# aux_powers.net
KiCad netlist of a schematic drawn in Altium Designer
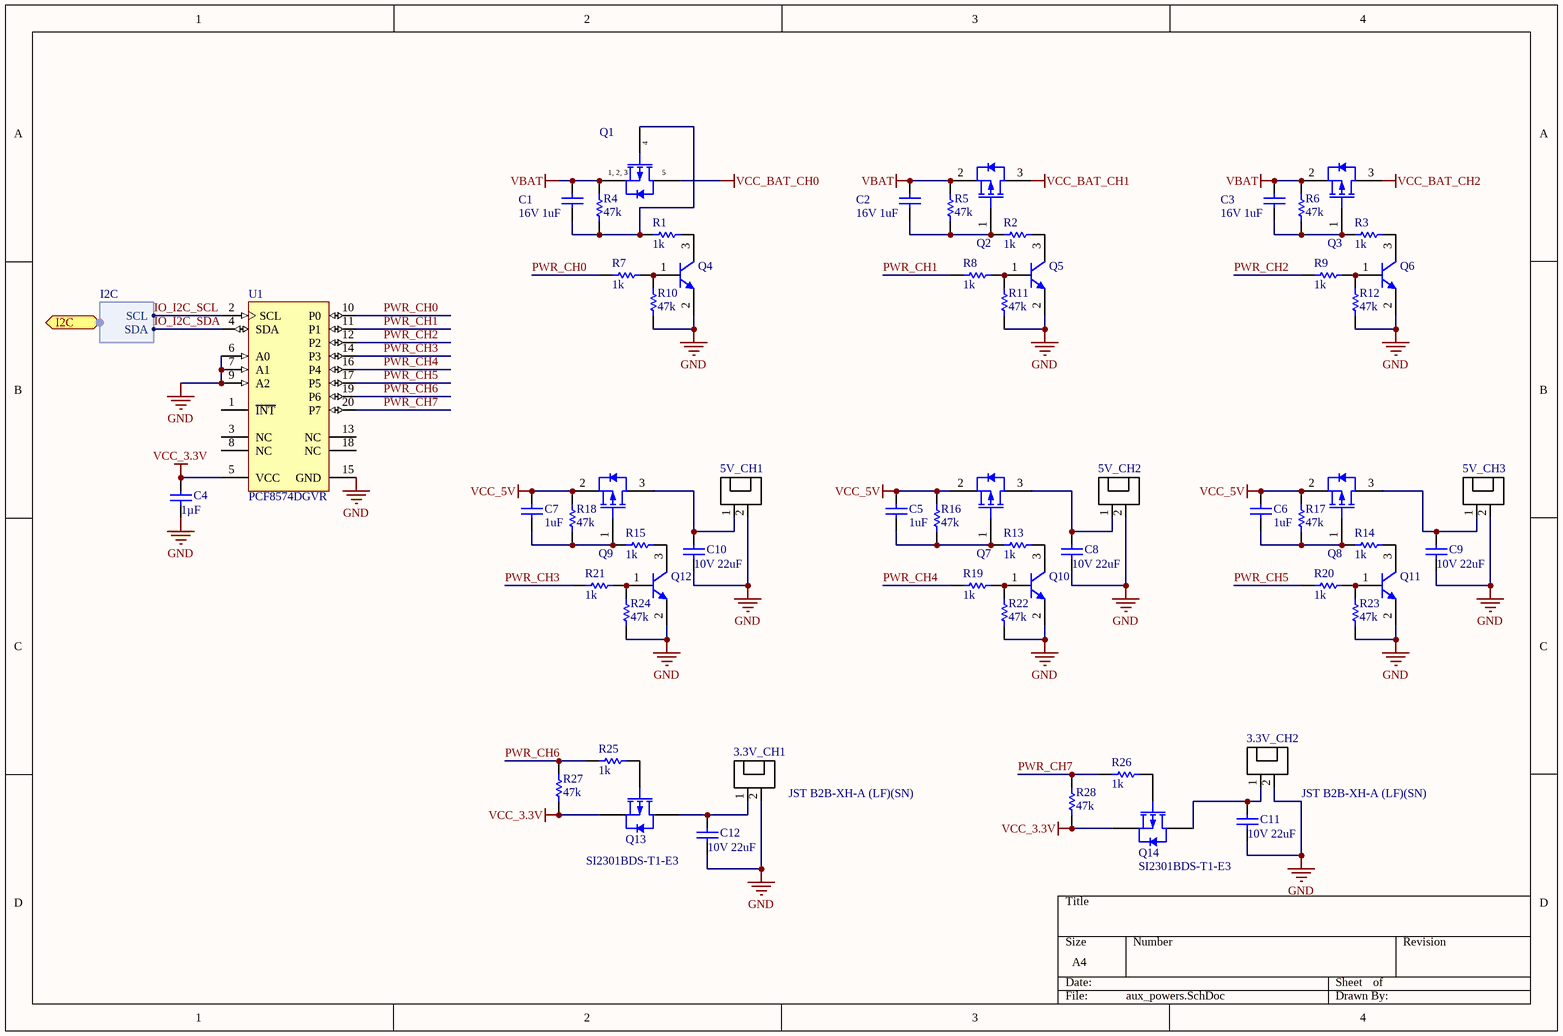
[diagram p0: aux_powers.SchDoc]

(export (version "E")
  (design (tool "Eeschema 10.0.6"))
  (components
    (comp (ref "3.3V_CH1")
      (value "JST B2B-XH-A (LF)(SN)")
      (footprint "PCB-s8s8ac3ylnu6waak0fxh-1")
      (description "XH Series 2 Position 2.5 mm Pitch Through Hole Top Entry Shrouded Header")
      (fields (field (name "MANUFACTURER PART NUMBER") "B2B-XH-A (LF)(SN)"))
      (libsource (lib "CommunityVault") (part "SYM-a2a66bdac84f7d61-1"))
    )
    (comp (ref "3.3V_CH2")
      (value "JST B2B-XH-A (LF)(SN)")
      (footprint "PCB-s8s8ac3ylnu6waak0fxh-1")
      (description "XH Series 2 Position 2.5 mm Pitch Through Hole Top Entry Shrouded Header")
      (fields (field (name "MANUFACTURER PART NUMBER") "B2B-XH-A (LF)(SN)"))
      (libsource (lib "CommunityVault") (part "SYM-a2a66bdac84f7d61-1"))
    )
    (comp (ref "5V_CH1")
      (value "JST B2B-XH-A (LF)(SN)")
      (footprint "PCB-s8s8ac3ylnu6waak0fxh-1")
      (description "XH Series 2 Position 2.5 mm Pitch Through Hole Top Entry Shrouded Header")
      (fields (field (name "MANUFACTURER PART NUMBER") "B2B-XH-A (LF)(SN)"))
      (libsource (lib "CommunityVault") (part "SYM-a2a66bdac84f7d61-1"))
    )
    (comp (ref "5V_CH2")
      (value "JST B2B-XH-A (LF)(SN)")
      (footprint "PCB-s8s8ac3ylnu6waak0fxh-1")
      (description "XH Series 2 Position 2.5 mm Pitch Through Hole Top Entry Shrouded Header")
      (fields (field (name "MANUFACTURER PART NUMBER") "B2B-XH-A (LF)(SN)"))
      (libsource (lib "CommunityVault") (part "SYM-a2a66bdac84f7d61-1"))
    )
    (comp (ref "5V_CH3")
      (value "JST B2B-XH-A (LF)(SN)")
      (footprint "PCB-s8s8ac3ylnu6waak0fxh-1")
      (description "XH Series 2 Position 2.5 mm Pitch Through Hole Top Entry Shrouded Header")
      (fields (field (name "MANUFACTURER PART NUMBER") "B2B-XH-A (LF)(SN)"))
      (libsource (lib "CommunityVault") (part "SYM-a2a66bdac84f7d61-1"))
    )
    (comp (ref "C1")
      (value "16V 1uF")
      (footprint "CAPC1005X56X25NL10T15")
      (description "Cap Ceramic 1uF 10V X5R 20% SMD 0402 85C Paper T/R")
      (fields (field (name "MANUFACTURER PART NUMBER") "0402ZD105MAT2A"))
      (libsource (lib "CommunityVault") (part "CMP-126963-2"))
    )
    (comp (ref "C2")
      (value "16V 1uF")
      (footprint "CAPC1005X56X25NL10T15")
      (description "Cap Ceramic 1uF 10V X5R 20% SMD 0402 85C Paper T/R")
      (fields (field (name "MANUFACTURER PART NUMBER") "0402ZD105MAT2A"))
      (libsource (lib "CommunityVault") (part "CMP-126963-2"))
    )
    (comp (ref "C3")
      (value "16V 1uF")
      (footprint "CAPC1005X56X25NL10T15")
      (description "Cap Ceramic 1uF 10V X5R 20% SMD 0402 85C Paper T/R")
      (fields (field (name "MANUFACTURER PART NUMBER") "0402ZD105MAT2A"))
      (libsource (lib "CommunityVault") (part "CMP-126963-2"))
    )
    (comp (ref "C4")
      (value "1µF")
      (footprint "CAPC1608X90X35LL15T15")
      (description "0603 1 uF 16 V ±10 % Tolerance X5R SMT Multilayer Ceramic Capacitor")
      (libsource (lib "CommunityVault") (part "CAP-NP-2"))
    )
    (comp (ref "C5")
      (value "1uF")
      (footprint "CAPC1005X56X25NL10T15")
      (description "Cap Ceramic 1uF 10V X5R 20% SMD 0402 85C Paper T/R")
      (fields (field (name "MANUFACTURER PART NUMBER") "0402ZD105MAT2A"))
      (libsource (lib "CommunityVault") (part "CMP-126963-2"))
    )
    (comp (ref "C6")
      (value "1uF")
      (footprint "CAPC1005X56X25NL10T15")
      (description "Cap Ceramic 1uF 10V X5R 20% SMD 0402 85C Paper T/R")
      (fields (field (name "MANUFACTURER PART NUMBER") "0402ZD105MAT2A"))
      (libsource (lib "CommunityVault") (part "CMP-126963-2"))
    )
    (comp (ref "C7")
      (value "1uF")
      (footprint "CAPC1005X56X25NL10T15")
      (description "Cap Ceramic 1uF 10V X5R 20% SMD 0402 85C Paper T/R")
      (fields (field (name "MANUFACTURER PART NUMBER") "0402ZD105MAT2A"))
      (libsource (lib "CommunityVault") (part "CMP-126963-2"))
    )
    (comp (ref "C8")
      (value "10V 22uF")
      (footprint "PCB-l6gghpm6qgmuzlt59psh-1")
      (description "Cap Ceramic 22uF 10V X5R 10% Pad SMD 1206 85C Automotive T/R")
      (fields (field (name "MANUFACTURER PART NUMBER") "LMK316ABJ226KLHT"))
      (libsource (lib "CommunityVault") (part "SYM-1dc8d7348becc20f-1"))
    )
    (comp (ref "C9")
      (value "10V 22uF")
      (footprint "PCB-l6gghpm6qgmuzlt59psh-1")
      (description "Cap Ceramic 22uF 10V X5R 10% Pad SMD 1206 85C Automotive T/R")
      (fields (field (name "MANUFACTURER PART NUMBER") "LMK316ABJ226KLHT"))
      (libsource (lib "CommunityVault") (part "SYM-1dc8d7348becc20f-1"))
    )
    (comp (ref "C10")
      (value "10V 22uF")
      (footprint "PCB-l6gghpm6qgmuzlt59psh-1")
      (description "Cap Ceramic 22uF 10V X5R 10% Pad SMD 1206 85C Automotive T/R")
      (fields (field (name "MANUFACTURER PART NUMBER") "LMK316ABJ226KLHT"))
      (libsource (lib "CommunityVault") (part "SYM-1dc8d7348becc20f-1"))
    )
    (comp (ref "C11")
      (value "10V 22uF")
      (footprint "PCB-l6gghpm6qgmuzlt59psh-1")
      (description "Cap Ceramic 22uF 10V X5R 10% Pad SMD 1206 85C Automotive T/R")
      (fields (field (name "MANUFACTURER PART NUMBER") "LMK316ABJ226KLHT"))
      (libsource (lib "CommunityVault") (part "SYM-1dc8d7348becc20f-1"))
    )
    (comp (ref "C12")
      (value "10V 22uF")
      (footprint "PCB-l6gghpm6qgmuzlt59psh-1")
      (description "Cap Ceramic 22uF 10V X5R 10% Pad SMD 1206 85C Automotive T/R")
      (fields (field (name "MANUFACTURER PART NUMBER") "LMK316ABJ226KLHT"))
      (libsource (lib "CommunityVault") (part "SYM-1dc8d7348becc20f-1"))
    )
    (comp (ref "Q1")
      (value "Vishay SI7149ADP-T1-GE3")
      (footprint "PCB-zhz9tig7820limf6j70v-1")
      (description "Si7149ADP Series 30 V 50 A 50 mOhm Surface Mount P-Channel Mosfet-PowerPAK SO-8")
      (libsource (lib "CommunityVault") (part "SYM-ebab2065408c346c-1"))
    )
    (comp (ref "Q2")
      (value "Vishay SISS23DN-T1-GE3")
      (footprint "PCB-3102182-1")
      (description "Si7617DN Series 30 V 12.3 mOhm 3.7 W P-Channel Mosfet - POWERPAK-1212-8")
      (libsource (lib "CommunityVault") (part "SYM-024ac984a975dd8d-1"))
    )
    (comp (ref "Q3")
      (value "Vishay SISS23DN-T1-GE3")
      (footprint "PCB-3102182-1")
      (description "Si7617DN Series 30 V 12.3 mOhm 3.7 W P-Channel Mosfet - POWERPAK-1212-8")
      (libsource (lib "CommunityVault") (part "SYM-024ac984a975dd8d-1"))
    )
    (comp (ref "Q4")
      (value "SMMBT4401LT1G")
      (footprint "ONSC-SOT-23-3-318-08_V")
      (description "Switching Transistor, NPN Silicon, 3-Pin SOT-23, Pb-Free, Tape and Reel")
      (libsource (lib "CommunityVault") (part "ONSC-NPN-B1E2C3-3"))
    )
    (comp (ref "Q5")
      (value "SMMBT4401LT1G")
      (footprint "ONSC-SOT-23-3-318-08_V")
      (description "Switching Transistor, NPN Silicon, 3-Pin SOT-23, Pb-Free, Tape and Reel")
      (libsource (lib "CommunityVault") (part "ONSC-NPN-B1E2C3-3"))
    )
    (comp (ref "Q6")
      (value "SMMBT4401LT1G")
      (footprint "ONSC-SOT-23-3-318-08_V")
      (description "Switching Transistor, NPN Silicon, 3-Pin SOT-23, Pb-Free, Tape and Reel")
      (libsource (lib "CommunityVault") (part "ONSC-NPN-B1E2C3-3"))
    )
    (comp (ref "Q7")
      (value "Vishay SISS23DN-T1-GE3")
      (footprint "PCB-3102182-1")
      (description "Si7617DN Series 30 V 12.3 mOhm 3.7 W P-Channel Mosfet - POWERPAK-1212-8")
      (libsource (lib "CommunityVault") (part "SYM-024ac984a975dd8d-1"))
    )
    (comp (ref "Q8")
      (value "Vishay SISS23DN-T1-GE3")
      (footprint "PCB-3102182-1")
      (description "Si7617DN Series 30 V 12.3 mOhm 3.7 W P-Channel Mosfet - POWERPAK-1212-8")
      (libsource (lib "CommunityVault") (part "SYM-024ac984a975dd8d-1"))
    )
    (comp (ref "Q9")
      (value "Vishay SISS23DN-T1-GE3")
      (footprint "PCB-3102182-1")
      (description "Si7617DN Series 30 V 12.3 mOhm 3.7 W P-Channel Mosfet - POWERPAK-1212-8")
      (libsource (lib "CommunityVault") (part "SYM-024ac984a975dd8d-1"))
    )
    (comp (ref "Q10")
      (value "SMMBT4401LT1G")
      (footprint "ONSC-SOT-23-3-318-08_V")
      (description "Switching Transistor, NPN Silicon, 3-Pin SOT-23, Pb-Free, Tape and Reel")
      (libsource (lib "CommunityVault") (part "ONSC-NPN-B1E2C3-3"))
    )
    (comp (ref "Q11")
      (value "SMMBT4401LT1G")
      (footprint "ONSC-SOT-23-3-318-08_V")
      (description "Switching Transistor, NPN Silicon, 3-Pin SOT-23, Pb-Free, Tape and Reel")
      (libsource (lib "CommunityVault") (part "ONSC-NPN-B1E2C3-3"))
    )
    (comp (ref "Q12")
      (value "SMMBT4401LT1G")
      (footprint "ONSC-SOT-23-3-318-08_V")
      (description "Switching Transistor, NPN Silicon, 3-Pin SOT-23, Pb-Free, Tape and Reel")
      (libsource (lib "CommunityVault") (part "ONSC-NPN-B1E2C3-3"))
    )
    (comp (ref "Q13")
      (value "SI2301BDS-T1-E3")
      (footprint "SOT-23-TT3_L")
      (description "Mosfet, P-ch, Vdss -20V, Rds(on) 0.08 Ohm, Id -2.2A, TO-236 (SOT-23), Pd 0.7W, Vgs +/-8V")
      (libsource (lib "CommunityVault") (part "SYM-4b14821b71e394d3-1"))
    )
    (comp (ref "Q14")
      (value "SI2301BDS-T1-E3")
      (footprint "SOT-23-TT3_L")
      (description "Mosfet, P-ch, Vdss -20V, Rds(on) 0.08 Ohm, Id -2.2A, TO-236 (SOT-23), Pd 0.7W, Vgs +/-8V")
      (libsource (lib "CommunityVault") (part "SYM-4b14821b71e394d3-1"))
    )
    (comp (ref "R1")
      (value "1k")
      (footprint "PCB-imsgvtunp3nvnj2wzwbs-1")
      (description "Res Thick Film 0402 1K Ohm 1% 0.125W(1/8W) ±100ppm/C Pad SMD T/R")
      (fields (field (name "MANUFACTURER PART NUMBER") "CRGP0402F1K0"))
      (libsource (lib "CommunityVault") (part "SYM-56d29ab4a6068915-1"))
    )
    (comp (ref "R2")
      (value "1k")
      (footprint "PCB-imsgvtunp3nvnj2wzwbs-1")
      (description "Res Thick Film 0402 1K Ohm 1% 0.125W(1/8W) ±100ppm/C Pad SMD T/R")
      (fields (field (name "MANUFACTURER PART NUMBER") "CRGP0402F1K0"))
      (libsource (lib "CommunityVault") (part "SYM-56d29ab4a6068915-1"))
    )
    (comp (ref "R3")
      (value "1k")
      (footprint "PCB-imsgvtunp3nvnj2wzwbs-1")
      (description "Res Thick Film 0402 1K Ohm 1% 0.125W(1/8W) ±100ppm/C Pad SMD T/R")
      (fields (field (name "MANUFACTURER PART NUMBER") "CRGP0402F1K0"))
      (libsource (lib "CommunityVault") (part "SYM-56d29ab4a6068915-1"))
    )
    (comp (ref "R4")
      (value "47k")
      (footprint "RESC1005X40X25LL05T10")
      (description "Thick Film Resistors - SMD 1/8watt 47Kohms 1% 100ppm High Power")
      (fields (field (name "MANUFACTURER PART NUMBER") "CRCW040247K0FKEDHP"))
      (libsource (lib "CommunityVault") (part "CMP-1859043-2"))
    )
    (comp (ref "R5")
      (value "47k")
      (footprint "RESC1005X40X25LL05T10")
      (description "Thick Film Resistors - SMD 1/8watt 47Kohms 1% 100ppm High Power")
      (fields (field (name "MANUFACTURER PART NUMBER") "CRCW040247K0FKEDHP"))
      (libsource (lib "CommunityVault") (part "CMP-1859043-2"))
    )
    (comp (ref "R6")
      (value "47k")
      (footprint "RESC1005X40X25LL05T10")
      (description "Thick Film Resistors - SMD 1/8watt 47Kohms 1% 100ppm High Power")
      (fields (field (name "MANUFACTURER PART NUMBER") "CRCW040247K0FKEDHP"))
      (libsource (lib "CommunityVault") (part "CMP-1859043-2"))
    )
    (comp (ref "R7")
      (value "1k")
      (footprint "PCB-imsgvtunp3nvnj2wzwbs-1")
      (description "Res Thick Film 0402 1K Ohm 1% 0.125W(1/8W) ±100ppm/C Pad SMD T/R")
      (fields (field (name "MANUFACTURER PART NUMBER") "CRGP0402F1K0"))
      (libsource (lib "CommunityVault") (part "SYM-56d29ab4a6068915-1"))
    )
    (comp (ref "R8")
      (value "1k")
      (footprint "PCB-imsgvtunp3nvnj2wzwbs-1")
      (description "Res Thick Film 0402 1K Ohm 1% 0.125W(1/8W) ±100ppm/C Pad SMD T/R")
      (fields (field (name "MANUFACTURER PART NUMBER") "CRGP0402F1K0"))
      (libsource (lib "CommunityVault") (part "SYM-56d29ab4a6068915-1"))
    )
    (comp (ref "R9")
      (value "1k")
      (footprint "PCB-imsgvtunp3nvnj2wzwbs-1")
      (description "Res Thick Film 0402 1K Ohm 1% 0.125W(1/8W) ±100ppm/C Pad SMD T/R")
      (fields (field (name "MANUFACTURER PART NUMBER") "CRGP0402F1K0"))
      (libsource (lib "CommunityVault") (part "SYM-56d29ab4a6068915-1"))
    )
    (comp (ref "R10")
      (value "47k")
      (footprint "RESC1005X40X25LL05T10")
      (description "Thick Film Resistors - SMD 1/8watt 47Kohms 1% 100ppm High Power")
      (fields (field (name "MANUFACTURER PART NUMBER") "CRCW040247K0FKEDHP"))
      (libsource (lib "CommunityVault") (part "CMP-1859043-2"))
    )
    (comp (ref "R11")
      (value "47k")
      (footprint "RESC1005X40X25LL05T10")
      (description "Thick Film Resistors - SMD 1/8watt 47Kohms 1% 100ppm High Power")
      (fields (field (name "MANUFACTURER PART NUMBER") "CRCW040247K0FKEDHP"))
      (libsource (lib "CommunityVault") (part "CMP-1859043-2"))
    )
    (comp (ref "R12")
      (value "47k")
      (footprint "RESC1005X40X25LL05T10")
      (description "Thick Film Resistors - SMD 1/8watt 47Kohms 1% 100ppm High Power")
      (fields (field (name "MANUFACTURER PART NUMBER") "CRCW040247K0FKEDHP"))
      (libsource (lib "CommunityVault") (part "CMP-1859043-2"))
    )
    (comp (ref "R13")
      (value "1k")
      (footprint "PCB-imsgvtunp3nvnj2wzwbs-1")
      (description "Res Thick Film 0402 1K Ohm 1% 0.125W(1/8W) ±100ppm/C Pad SMD T/R")
      (fields (field (name "MANUFACTURER PART NUMBER") "CRGP0402F1K0"))
      (libsource (lib "CommunityVault") (part "SYM-56d29ab4a6068915-1"))
    )
    (comp (ref "R14")
      (value "1k")
      (footprint "PCB-imsgvtunp3nvnj2wzwbs-1")
      (description "Res Thick Film 0402 1K Ohm 1% 0.125W(1/8W) ±100ppm/C Pad SMD T/R")
      (fields (field (name "MANUFACTURER PART NUMBER") "CRGP0402F1K0"))
      (libsource (lib "CommunityVault") (part "SYM-56d29ab4a6068915-1"))
    )
    (comp (ref "R15")
      (value "1k")
      (footprint "PCB-imsgvtunp3nvnj2wzwbs-1")
      (description "Res Thick Film 0402 1K Ohm 1% 0.125W(1/8W) ±100ppm/C Pad SMD T/R")
      (fields (field (name "MANUFACTURER PART NUMBER") "CRGP0402F1K0"))
      (libsource (lib "CommunityVault") (part "SYM-56d29ab4a6068915-1"))
    )
    (comp (ref "R16")
      (value "47k")
      (footprint "RESC1005X40X25LL05T10")
      (description "Thick Film Resistors - SMD 1/8watt 47Kohms 1% 100ppm High Power")
      (fields (field (name "MANUFACTURER PART NUMBER") "CRCW040247K0FKEDHP"))
      (libsource (lib "CommunityVault") (part "CMP-1859043-2"))
    )
    (comp (ref "R17")
      (value "47k")
      (footprint "RESC1005X40X25LL05T10")
      (description "Thick Film Resistors - SMD 1/8watt 47Kohms 1% 100ppm High Power")
      (fields (field (name "MANUFACTURER PART NUMBER") "CRCW040247K0FKEDHP"))
      (libsource (lib "CommunityVault") (part "CMP-1859043-2"))
    )
    (comp (ref "R18")
      (value "47k")
      (footprint "RESC1005X40X25LL05T10")
      (description "Thick Film Resistors - SMD 1/8watt 47Kohms 1% 100ppm High Power")
      (fields (field (name "MANUFACTURER PART NUMBER") "CRCW040247K0FKEDHP"))
      (libsource (lib "CommunityVault") (part "CMP-1859043-2"))
    )
    (comp (ref "R19")
      (value "1k")
      (footprint "PCB-imsgvtunp3nvnj2wzwbs-1")
      (description "Res Thick Film 0402 1K Ohm 1% 0.125W(1/8W) ±100ppm/C Pad SMD T/R")
      (fields (field (name "MANUFACTURER PART NUMBER") "CRGP0402F1K0"))
      (libsource (lib "CommunityVault") (part "SYM-56d29ab4a6068915-1"))
    )
    (comp (ref "R20")
      (value "1k")
      (footprint "PCB-imsgvtunp3nvnj2wzwbs-1")
      (description "Res Thick Film 0402 1K Ohm 1% 0.125W(1/8W) ±100ppm/C Pad SMD T/R")
      (fields (field (name "MANUFACTURER PART NUMBER") "CRGP0402F1K0"))
      (libsource (lib "CommunityVault") (part "SYM-56d29ab4a6068915-1"))
    )
    (comp (ref "R21")
      (value "1k")
      (footprint "PCB-imsgvtunp3nvnj2wzwbs-1")
      (description "Res Thick Film 0402 1K Ohm 1% 0.125W(1/8W) ±100ppm/C Pad SMD T/R")
      (fields (field (name "MANUFACTURER PART NUMBER") "CRGP0402F1K0"))
      (libsource (lib "CommunityVault") (part "SYM-56d29ab4a6068915-1"))
    )
    (comp (ref "R22")
      (value "47k")
      (footprint "RESC1005X40X25LL05T10")
      (description "Thick Film Resistors - SMD 1/8watt 47Kohms 1% 100ppm High Power")
      (fields (field (name "MANUFACTURER PART NUMBER") "CRCW040247K0FKEDHP"))
      (libsource (lib "CommunityVault") (part "CMP-1859043-2"))
    )
    (comp (ref "R23")
      (value "47k")
      (footprint "RESC1005X40X25LL05T10")
      (description "Thick Film Resistors - SMD 1/8watt 47Kohms 1% 100ppm High Power")
      (fields (field (name "MANUFACTURER PART NUMBER") "CRCW040247K0FKEDHP"))
      (libsource (lib "CommunityVault") (part "CMP-1859043-2"))
    )
    (comp (ref "R24")
      (value "47k")
      (footprint "RESC1005X40X25LL05T10")
      (description "Thick Film Resistors - SMD 1/8watt 47Kohms 1% 100ppm High Power")
      (fields (field (name "MANUFACTURER PART NUMBER") "CRCW040247K0FKEDHP"))
      (libsource (lib "CommunityVault") (part "CMP-1859043-2"))
    )
    (comp (ref "R25")
      (value "1k")
      (footprint "PCB-imsgvtunp3nvnj2wzwbs-1")
      (description "Res Thick Film 0402 1K Ohm 1% 0.125W(1/8W) ±100ppm/C Pad SMD T/R")
      (fields (field (name "MANUFACTURER PART NUMBER") "CRGP0402F1K0"))
      (libsource (lib "CommunityVault") (part "SYM-56d29ab4a6068915-1"))
    )
    (comp (ref "R26")
      (value "1k")
      (footprint "PCB-imsgvtunp3nvnj2wzwbs-1")
      (description "Res Thick Film 0402 1K Ohm 1% 0.125W(1/8W) ±100ppm/C Pad SMD T/R")
      (fields (field (name "MANUFACTURER PART NUMBER") "CRGP0402F1K0"))
      (libsource (lib "CommunityVault") (part "SYM-56d29ab4a6068915-1"))
    )
    (comp (ref "R27")
      (value "47k")
      (footprint "RESC1005X40X25LL05T10")
      (description "Thick Film Resistors - SMD 1/8watt 47Kohms 1% 100ppm High Power")
      (fields (field (name "MANUFACTURER PART NUMBER") "CRCW040247K0FKEDHP"))
      (libsource (lib "CommunityVault") (part "CMP-1859043-2"))
    )
    (comp (ref "R28")
      (value "47k")
      (footprint "RESC1005X40X25LL05T10")
      (description "Thick Film Resistors - SMD 1/8watt 47Kohms 1% 100ppm High Power")
      (fields (field (name "MANUFACTURER PART NUMBER") "CRCW040247K0FKEDHP"))
      (libsource (lib "CommunityVault") (part "CMP-1859043-2"))
    )
    (comp (ref "U1")
      (value "PCF8574DGVR")
      (footprint "DGV20_L")
      (libsource (lib "CommunityVault") (part "TI-PCF8574-TVSOP_DGV-20"))
    )
  )
  (nets
    (net (code "2") (name "/IO_I2C_SCL") (class "Default")
      (node (ref "U1") (pin "2") (pinfunction "SCL_2") (pintype "input"))
    )
    (net (code "3") (name "/IO_I2C_SDA") (class "Default")
      (node (ref "U1") (pin "4") (pinfunction "SDA_4") (pintype "bidirectional"))
    )
    (net (code "4") (name "/PWR_CH0") (class "Default")
      (node (ref "R7") (pin "1") (pinfunction "1_1") (pintype "passive"))
      (node (ref "U1") (pin "10") (pinfunction "P0_10") (pintype "bidirectional"))
    )
    (net (code "5") (name "/PWR_CH1") (class "Default")
      (node (ref "R8") (pin "1") (pinfunction "1_1") (pintype "passive"))
      (node (ref "U1") (pin "11") (pinfunction "P1_11") (pintype "bidirectional"))
    )
    (net (code "6") (name "/PWR_CH2") (class "Default")
      (node (ref "R9") (pin "1") (pinfunction "1_1") (pintype "passive"))
      (node (ref "U1") (pin "12") (pinfunction "P2_12") (pintype "bidirectional"))
    )
    (net (code "7") (name "/PWR_CH3") (class "Default")
      (node (ref "R21") (pin "1") (pinfunction "1_1") (pintype "passive"))
      (node (ref "U1") (pin "14") (pinfunction "P3_14") (pintype "bidirectional"))
    )
    (net (code "8") (name "/PWR_CH4") (class "Default")
      (node (ref "R19") (pin "1") (pinfunction "1_1") (pintype "passive"))
      (node (ref "U1") (pin "16") (pinfunction "P4_16") (pintype "bidirectional"))
    )
    (net (code "9") (name "/PWR_CH5") (class "Default")
      (node (ref "R20") (pin "1") (pinfunction "1_1") (pintype "passive"))
      (node (ref "U1") (pin "17") (pinfunction "P5_17") (pintype "bidirectional"))
    )
    (net (code "10") (name "/PWR_CH6") (class "Default")
      (node (ref "R25") (pin "1") (pinfunction "1_1") (pintype "passive"))
      (node (ref "R27") (pin "2") (pinfunction "2_2") (pintype "passive"))
      (node (ref "U1") (pin "19") (pinfunction "P6_19") (pintype "bidirectional"))
    )
    (net (code "11") (name "/PWR_CH7") (class "Default")
      (node (ref "R26") (pin "1") (pinfunction "1_1") (pintype "passive"))
      (node (ref "R28") (pin "2") (pinfunction "2_2") (pintype "passive"))
      (node (ref "U1") (pin "20") (pinfunction "P7_20") (pintype "bidirectional"))
    )
    (net (code "13") (name "GND") (class "Default")
      (node (ref "3.3V_CH1") (pin "2") (pinfunction "2_2") (pintype "passive"))
      (node (ref "3.3V_CH2") (pin "2") (pinfunction "2_2") (pintype "passive"))
      (node (ref "5V_CH1") (pin "2") (pinfunction "2_2") (pintype "passive"))
      (node (ref "5V_CH2") (pin "2") (pinfunction "2_2") (pintype "passive"))
      (node (ref "5V_CH3") (pin "2") (pinfunction "2_2") (pintype "passive"))
      (node (ref "C10") (pin "1") (pinfunction "1_1") (pintype "passive"))
      (node (ref "C11") (pin "1") (pinfunction "1_1") (pintype "passive"))
      (node (ref "C12") (pin "1") (pinfunction "1_1") (pintype "passive"))
      (node (ref "C4") (pin "2") (pinfunction "2_2") (pintype "passive"))
      (node (ref "C8") (pin "1") (pinfunction "1_1") (pintype "passive"))
      (node (ref "C9") (pin "1") (pinfunction "1_1") (pintype "passive"))
      (node (ref "Q10") (pin "2") (pinfunction "E_2") (pintype "passive"))
      (node (ref "Q11") (pin "2") (pinfunction "E_2") (pintype "passive"))
      (node (ref "Q12") (pin "2") (pinfunction "E_2") (pintype "passive"))
      (node (ref "Q4") (pin "2") (pinfunction "E_2") (pintype "passive"))
      (node (ref "Q5") (pin "2") (pinfunction "E_2") (pintype "passive"))
      (node (ref "Q6") (pin "2") (pinfunction "E_2") (pintype "passive"))
      (node (ref "R10") (pin "1") (pinfunction "1_1") (pintype "passive"))
      (node (ref "R11") (pin "1") (pinfunction "1_1") (pintype "passive"))
      (node (ref "R12") (pin "1") (pinfunction "1_1") (pintype "passive"))
      (node (ref "R22") (pin "1") (pinfunction "1_1") (pintype "passive"))
      (node (ref "R23") (pin "1") (pinfunction "1_1") (pintype "passive"))
      (node (ref "R24") (pin "1") (pinfunction "1_1") (pintype "passive"))
      (node (ref "U1") (pin "15") (pinfunction "GND_15") (pintype "power_in"))
      (node (ref "U1") (pin "6") (pinfunction "A0_6") (pintype "input"))
      (node (ref "U1") (pin "7") (pinfunction "A1_7") (pintype "input"))
      (node (ref "U1") (pin "9") (pinfunction "A2_9") (pintype "input"))
    )
    (net (code "14") (name "Net-(3.3V_CH1-Pad1)") (class "Default")
      (node (ref "3.3V_CH1") (pin "1") (pinfunction "1_1") (pintype "passive"))
      (node (ref "C12") (pin "2") (pinfunction "2_2") (pintype "passive"))
      (node (ref "Q13") (pin "3") (pinfunction "3_3") (pintype "passive"))
    )
    (net (code "15") (name "Net-(3.3V_CH2-Pad1)") (class "Default")
      (node (ref "3.3V_CH2") (pin "1") (pinfunction "1_1") (pintype "passive"))
      (node (ref "C11") (pin "2") (pinfunction "2_2") (pintype "passive"))
      (node (ref "Q14") (pin "3") (pinfunction "3_3") (pintype "passive"))
    )
    (net (code "16") (name "Net-(C1-Pad1)") (class "Default")
      (node (ref "C1") (pin "1") (pinfunction "1_1") (pintype "passive"))
      (node (ref "Q1") (pin "G") (pinfunction "G_G") (pintype "passive"))
      (node (ref "R1") (pin "2") (pinfunction "2_2") (pintype "passive"))
      (node (ref "R4") (pin "1") (pinfunction "1_1") (pintype "passive"))
    )
    (net (code "17") (name "Net-(Q2-G)") (class "Default")
      (node (ref "C2") (pin "1") (pinfunction "1_1") (pintype "passive"))
      (node (ref "Q2") (pin "1") (pinfunction "G_1") (pintype "passive"))
      (node (ref "R2") (pin "2") (pinfunction "2_2") (pintype "passive"))
      (node (ref "R5") (pin "1") (pinfunction "1_1") (pintype "passive"))
    )
    (net (code "18") (name "Net-(Q3-G)") (class "Default")
      (node (ref "C3") (pin "1") (pinfunction "1_1") (pintype "passive"))
      (node (ref "Q3") (pin "1") (pinfunction "G_1") (pintype "passive"))
      (node (ref "R3") (pin "2") (pinfunction "2_2") (pintype "passive"))
      (node (ref "R6") (pin "1") (pinfunction "1_1") (pintype "passive"))
    )
    (net (code "19") (name "Net-(Q4-B)") (class "Default")
      (node (ref "Q4") (pin "1") (pinfunction "B_1") (pintype "passive"))
      (node (ref "R10") (pin "2") (pinfunction "2_2") (pintype "passive"))
      (node (ref "R7") (pin "2") (pinfunction "2_2") (pintype "passive"))
    )
    (net (code "20") (name "Net-(Q4-C)") (class "Default")
      (node (ref "Q4") (pin "3") (pinfunction "C_3") (pintype "passive"))
      (node (ref "R1") (pin "1") (pinfunction "1_1") (pintype "passive"))
    )
    (net (code "21") (name "Net-(Q5-B)") (class "Default")
      (node (ref "Q5") (pin "1") (pinfunction "B_1") (pintype "passive"))
      (node (ref "R11") (pin "2") (pinfunction "2_2") (pintype "passive"))
      (node (ref "R8") (pin "2") (pinfunction "2_2") (pintype "passive"))
    )
    (net (code "22") (name "Net-(Q5-C)") (class "Default")
      (node (ref "Q5") (pin "3") (pinfunction "C_3") (pintype "passive"))
      (node (ref "R2") (pin "1") (pinfunction "1_1") (pintype "passive"))
    )
    (net (code "23") (name "Net-(Q6-B)") (class "Default")
      (node (ref "Q6") (pin "1") (pinfunction "B_1") (pintype "passive"))
      (node (ref "R12") (pin "2") (pinfunction "2_2") (pintype "passive"))
      (node (ref "R9") (pin "2") (pinfunction "2_2") (pintype "passive"))
    )
    (net (code "24") (name "Net-(Q6-C)") (class "Default")
      (node (ref "Q6") (pin "3") (pinfunction "C_3") (pintype "passive"))
      (node (ref "R3") (pin "1") (pinfunction "1_1") (pintype "passive"))
    )
    (net (code "25") (name "Net-(Q7-G)") (class "Default")
      (node (ref "C5") (pin "1") (pinfunction "1_1") (pintype "passive"))
      (node (ref "Q7") (pin "1") (pinfunction "G_1") (pintype "passive"))
      (node (ref "R13") (pin "2") (pinfunction "2_2") (pintype "passive"))
      (node (ref "R16") (pin "1") (pinfunction "1_1") (pintype "passive"))
    )
    (net (code "26") (name "Net-(Q7-S)") (class "Default")
      (node (ref "5V_CH2") (pin "1") (pinfunction "1_1") (pintype "passive"))
      (node (ref "C8") (pin "2") (pinfunction "2_2") (pintype "passive"))
      (node (ref "Q7") (pin "3") (pinfunction "S_3") (pintype "passive"))
    )
    (net (code "27") (name "Net-(Q8-G)") (class "Default")
      (node (ref "C6") (pin "1") (pinfunction "1_1") (pintype "passive"))
      (node (ref "Q8") (pin "1") (pinfunction "G_1") (pintype "passive"))
      (node (ref "R14") (pin "2") (pinfunction "2_2") (pintype "passive"))
      (node (ref "R17") (pin "1") (pinfunction "1_1") (pintype "passive"))
    )
    (net (code "28") (name "Net-(Q8-S)") (class "Default")
      (node (ref "5V_CH3") (pin "1") (pinfunction "1_1") (pintype "passive"))
      (node (ref "C9") (pin "2") (pinfunction "2_2") (pintype "passive"))
      (node (ref "Q8") (pin "3") (pinfunction "S_3") (pintype "passive"))
    )
    (net (code "29") (name "Net-(Q9-G)") (class "Default")
      (node (ref "C7") (pin "1") (pinfunction "1_1") (pintype "passive"))
      (node (ref "Q9") (pin "1") (pinfunction "G_1") (pintype "passive"))
      (node (ref "R15") (pin "2") (pinfunction "2_2") (pintype "passive"))
      (node (ref "R18") (pin "1") (pinfunction "1_1") (pintype "passive"))
    )
    (net (code "30") (name "Net-(Q9-S)") (class "Default")
      (node (ref "5V_CH1") (pin "1") (pinfunction "1_1") (pintype "passive"))
      (node (ref "C10") (pin "2") (pinfunction "2_2") (pintype "passive"))
      (node (ref "Q9") (pin "3") (pinfunction "S_3") (pintype "passive"))
    )
    (net (code "31") (name "Net-(Q10-B)") (class "Default")
      (node (ref "Q10") (pin "1") (pinfunction "B_1") (pintype "passive"))
      (node (ref "R19") (pin "2") (pinfunction "2_2") (pintype "passive"))
      (node (ref "R22") (pin "2") (pinfunction "2_2") (pintype "passive"))
    )
    (net (code "32") (name "Net-(Q10-C)") (class "Default")
      (node (ref "Q10") (pin "3") (pinfunction "C_3") (pintype "passive"))
      (node (ref "R13") (pin "1") (pinfunction "1_1") (pintype "passive"))
    )
    (net (code "33") (name "Net-(Q11-B)") (class "Default")
      (node (ref "Q11") (pin "1") (pinfunction "B_1") (pintype "passive"))
      (node (ref "R20") (pin "2") (pinfunction "2_2") (pintype "passive"))
      (node (ref "R23") (pin "2") (pinfunction "2_2") (pintype "passive"))
    )
    (net (code "34") (name "Net-(Q11-C)") (class "Default")
      (node (ref "Q11") (pin "3") (pinfunction "C_3") (pintype "passive"))
      (node (ref "R14") (pin "1") (pinfunction "1_1") (pintype "passive"))
    )
    (net (code "35") (name "Net-(Q12-B)") (class "Default")
      (node (ref "Q12") (pin "1") (pinfunction "B_1") (pintype "passive"))
      (node (ref "R21") (pin "2") (pinfunction "2_2") (pintype "passive"))
      (node (ref "R24") (pin "2") (pinfunction "2_2") (pintype "passive"))
    )
    (net (code "36") (name "Net-(Q12-C)") (class "Default")
      (node (ref "Q12") (pin "3") (pinfunction "C_3") (pintype "passive"))
      (node (ref "R15") (pin "1") (pinfunction "1_1") (pintype "passive"))
    )
    (net (code "37") (name "Net-(Q13-Pad1)") (class "Default")
      (node (ref "Q13") (pin "1") (pinfunction "1_1") (pintype "passive"))
      (node (ref "R25") (pin "2") (pinfunction "2_2") (pintype "passive"))
    )
    (net (code "38") (name "Net-(Q14-Pad1)") (class "Default")
      (node (ref "Q14") (pin "1") (pinfunction "1_1") (pintype "passive"))
      (node (ref "R26") (pin "2") (pinfunction "2_2") (pintype "passive"))
    )
    (net (code "39") (name "VBAT") (class "Default")
      (node (ref "C1") (pin "2") (pinfunction "2_2") (pintype "passive"))
      (node (ref "C2") (pin "2") (pinfunction "2_2") (pintype "passive"))
      (node (ref "C3") (pin "2") (pinfunction "2_2") (pintype "passive"))
      (node (ref "Q1") (pin "S") (pinfunction "S_S") (pintype "passive"))
      (node (ref "Q2") (pin "2") (pinfunction "D_2") (pintype "passive"))
      (node (ref "Q3") (pin "2") (pinfunction "D_2") (pintype "passive"))
      (node (ref "R4") (pin "2") (pinfunction "2_2") (pintype "passive"))
      (node (ref "R5") (pin "2") (pinfunction "2_2") (pintype "passive"))
      (node (ref "R6") (pin "2") (pinfunction "2_2") (pintype "passive"))
    )
    (net (code "40") (name "VCC_3.3V") (class "Default")
      (node (ref "C4") (pin "1") (pinfunction "1_1") (pintype "passive"))
      (node (ref "Q13") (pin "2") (pinfunction "2_2") (pintype "passive"))
      (node (ref "Q14") (pin "2") (pinfunction "2_2") (pintype "passive"))
      (node (ref "R27") (pin "1") (pinfunction "1_1") (pintype "passive"))
      (node (ref "R28") (pin "1") (pinfunction "1_1") (pintype "passive"))
      (node (ref "U1") (pin "5") (pinfunction "VCC_5") (pintype "power_in"))
    )
    (net (code "41") (name "VCC_5V") (class "Default")
      (node (ref "C5") (pin "2") (pinfunction "2_2") (pintype "passive"))
      (node (ref "C6") (pin "2") (pinfunction "2_2") (pintype "passive"))
      (node (ref "C7") (pin "2") (pinfunction "2_2") (pintype "passive"))
      (node (ref "Q7") (pin "2") (pinfunction "D_2") (pintype "passive"))
      (node (ref "Q8") (pin "2") (pinfunction "D_2") (pintype "passive"))
      (node (ref "Q9") (pin "2") (pinfunction "D_2") (pintype "passive"))
      (node (ref "R16") (pin "2") (pinfunction "2_2") (pintype "passive"))
      (node (ref "R17") (pin "2") (pinfunction "2_2") (pintype "passive"))
      (node (ref "R18") (pin "2") (pinfunction "2_2") (pintype "passive"))
    )
    (net (code "42") (name "VCC_BAT_CH0") (class "Default")
      (node (ref "Q1") (pin "D") (pinfunction "D_D") (pintype "passive"))
    )
    (net (code "43") (name "VCC_BAT_CH1") (class "Default")
      (node (ref "Q2") (pin "3") (pinfunction "S_3") (pintype "passive"))
    )
    (net (code "44") (name "VCC_BAT_CH2") (class "Default")
      (node (ref "Q3") (pin "3") (pinfunction "S_3") (pintype "passive"))
    )
    (net (code "45") (name "unconnected-(U1-NC-Pad3)") (class "Default")
      (node (ref "U1") (pin "3") (pinfunction "NC_3") (pintype "passive"))
    )
    (net (code "46") (name "unconnected-(U1-NC-Pad8)") (class "Default")
      (node (ref "U1") (pin "8") (pinfunction "NC_8") (pintype "passive"))
    )
    (net (code "47") (name "unconnected-(U1-NC-Pad13)") (class "Default")
      (node (ref "U1") (pin "13") (pinfunction "NC_13") (pintype "passive"))
    )
    (net (code "48") (name "unconnected-(U1-NC-Pad18)") (class "Default")
      (node (ref "U1") (pin "18") (pinfunction "NC_18") (pintype "passive"))
    )
    (net (code "49") (name "unconnected-(U1-~{INT}-Pad1)") (class "Default")
      (node (ref "U1") (pin "1") (pinfunction "~{INT}_1") (pintype "open_collector"))
    )
  )
)
